# ADC.net
KiCad netlist of a schematic drawn in Altium Designer
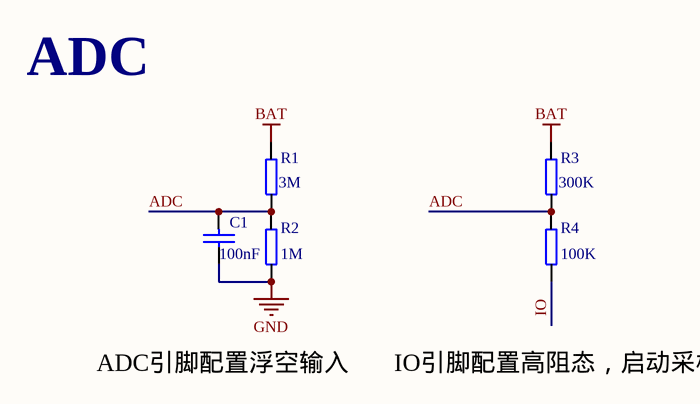
[diagram p0: ADC.SchDoc]

(export (version "E")
  (design (tool "Eeschema 10.0.6"))
  (components
    (comp (ref "C1")
      (value "100nF")
      (footprint "0402_C")
      (description "Capacitor")
      (libsource (lib "wch_sch_others") (part "CAP"))
    )
    (comp (ref "R1") (value "3M") (footprint "0402") (libsource (lib "wch_sch_others") (part "RES")))
    (comp (ref "R2") (value "1M") (footprint "0402") (libsource (lib "wch_sch_others") (part "RES")))
    (comp (ref "R3") (value "300K") (footprint "0402") (libsource (lib "wch_sch_others") (part "RES")))
    (comp (ref "R4") (value "100K") (footprint "0402") (libsource (lib "wch_sch_others") (part "RES")))
  )
  (nets
    (net (code "1") (name "/ADC") (class "Default")
      (node (ref "C1") (pin "1") (pinfunction "1_1") (pintype "passive"))
      (node (ref "R1") (pin "1") (pintype "passive"))
      (node (ref "R2") (pin "2") (pintype "passive"))
      (node (ref "R3") (pin "1") (pintype "passive"))
      (node (ref "R4") (pin "2") (pintype "passive"))
    )
    (net (code "2") (name "/IO") (class "Default") (node (ref "R4") (pin "1") (pintype "passive")))
    (net (code "3") (name "BAT") (class "Default")
      (node (ref "R1") (pin "2") (pintype "passive"))
      (node (ref "R3") (pin "2") (pintype "passive"))
    )
    (net (code "4") (name "GND") (class "Default")
      (node (ref "C1") (pin "2") (pinfunction "2_2") (pintype "passive"))
      (node (ref "R2") (pin "1") (pintype "passive"))
    )
  )
)
